# LMR514203_3V.net
KiCad netlist of a schematic drawn in Altium Designer
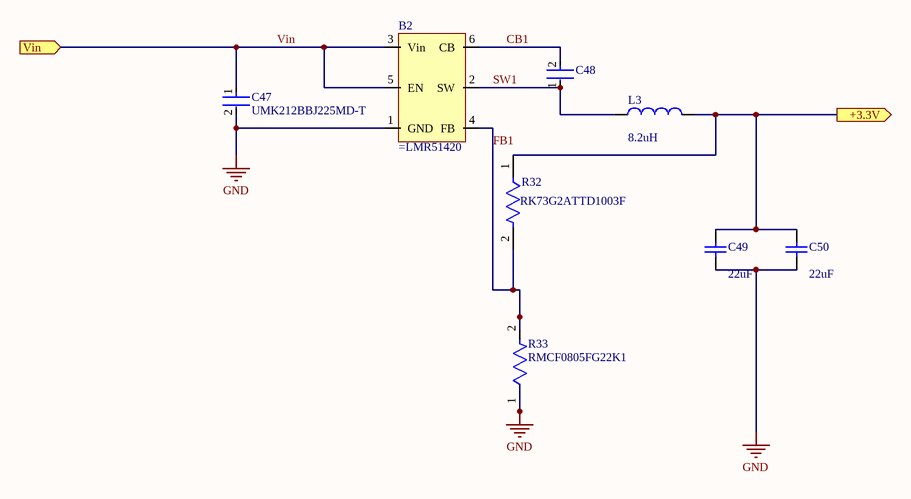
[diagram p0: LMR514203.3V.SchDoc]

(export (version "E")
  (design (tool "Eeschema 10.0.6"))
  (components
    (comp (ref "B2") (value "~") (footprint "LMR51420IC") (libsource (lib "LMR51420") (part "Component_1")))
    (comp (ref "C47")
      (value "UMK212BBJ225MD-T")
      (footprint "FP-0805-L_2_0_0_2-W_1_25-IPC_A")
      (description "Multilayer Ceramic Capacitor 2.2uF 50V X5R 20% SMD 0803 T/R")
      (fields (field (name "TOLERANCE") "20%"))
      (libsource (lib "Altium Content Vault") (part "02cd4be3c70576c341d710602a673aa"))
    )
    (comp (ref "C48")
      (value "C0603C104K4PAC7867")
      (footprint "CAP CER 0.1UF 16V X7R 0603")
      (description "CAP CER 0.1UF 16V X5R 0603")
      (fields
        (field (name "OCTOPART") "https://octopart.com/c0603c104k4pactu-kemet-12592163")
        (field (name "MANUFACTURER") "KEMET")
      )
      (libsource (lib "Miscellaneous Devices") (part "b4654b650e69147ec39a6b967a45e02"))
    )
    (comp (ref "C49")
      (value "22uF")
      (footprint "Cap22uF_C1206C226M4PAC7800")
      (description "Capacitor")
      (fields (field (name "Comment") "Comment") (field (name "PUBLISHER") "Altium Limited"))
      (libsource (lib "Miscellaneous Devices") (part "Cap"))
    )
    (comp (ref "C50")
      (value "22uF")
      (footprint "Cap22uF_C1206C226M4PAC7800")
      (description "Capacitor")
      (fields (field (name "Comment") "Comment") (field (name "PUBLISHER") "Altium Limited"))
      (libsource (lib "Miscellaneous Devices") (part "Cap"))
    )
    (comp (ref "L3")
      (value "8.2uH")
      (footprint "MSS1246H-103MED 10uH")
      (description "Inductor")
      (fields (field (name "Comment") "MSS1260H-822MED") (field (name "PUBLISHER") "Altium Limited"))
      (libsource (lib "Miscellaneous Devices") (part "Inductor"))
    )
    (comp (ref "R32")
      (value "RK73G2ATTD1003F")
      (footprint "FP-RK73G2A-IPC_A")
      (description "100kΩ ±1% 0.125W Chip Resistor 0805 Thick Film AEC-Q200 Qualified")
      (fields (field (name "TOLERANCE") "1%"))
      (libsource (lib "Altium Content Vault") (part "1029c3af85768c4190bb7ad29bc67b5"))
    )
    (comp (ref "R33")
      (value "RMCF0805FG22K1")
      (footprint "FP-RMCF0805-IPC_B")
      (description "22.1kΩ ±1% 0.125W 0805 Thick Film Chip Resistor AEC-Q200 compliant")
      (fields (field (name "TOLERANCE") "1%"))
      (libsource (lib "Altium Content Vault") (part "1029c3af85768c4190bb7ad29bc67b5"))
    )
  )
  (nets
    (net (code "1") (name "/+3.3V") (class "Default")
      (node (ref "C49") (pin "2") (pinfunction "2_2") (pintype "passive"))
      (node (ref "C50") (pin "2") (pinfunction "2_2") (pintype "passive"))
      (node (ref "L3") (pin "2") (pinfunction "2_2") (pintype "passive"))
      (node (ref "R32") (pin "1") (pinfunction "1_1") (pintype "passive"))
    )
    (net (code "2") (name "/CB1") (class "Default")
      (node (ref "B2") (pin "6") (pinfunction "CB_6") (pintype "passive"))
      (node (ref "C48") (pin "2") (pinfunction "2_2") (pintype "passive"))
    )
    (net (code "3") (name "/FB1") (class "Default")
      (node (ref "B2") (pin "4") (pinfunction "FB_4") (pintype "passive"))
      (node (ref "R32") (pin "2") (pinfunction "2_2") (pintype "passive"))
      (node (ref "R33") (pin "2") (pinfunction "2_2") (pintype "passive"))
    )
    (net (code "4") (name "/SW1") (class "Default")
      (node (ref "B2") (pin "2") (pinfunction "SW_2") (pintype "passive"))
      (node (ref "C48") (pin "1") (pinfunction "1_1") (pintype "passive"))
      (node (ref "L3") (pin "1") (pinfunction "1_1") (pintype "passive"))
    )
    (net (code "5") (name "/Vin") (class "Default")
      (node (ref "B2") (pin "3") (pinfunction "Vin_3") (pintype "passive"))
      (node (ref "B2") (pin "5") (pinfunction "EN_5") (pintype "passive"))
      (node (ref "C47") (pin "1") (pinfunction "1_1") (pintype "passive"))
    )
    (net (code "6") (name "GND") (class "Default")
      (node (ref "B2") (pin "1") (pinfunction "GND_1") (pintype "passive"))
      (node (ref "C47") (pin "2") (pinfunction "2_2") (pintype "passive"))
      (node (ref "C49") (pin "1") (pinfunction "1_1") (pintype "passive"))
      (node (ref "C50") (pin "1") (pinfunction "1_1") (pintype "passive"))
      (node (ref "R33") (pin "1") (pinfunction "1_1") (pintype "passive"))
    )
  )
)
